# 00_ESP8266_CH340.net
KiCad netlist of a schematic drawn in Altium Designer
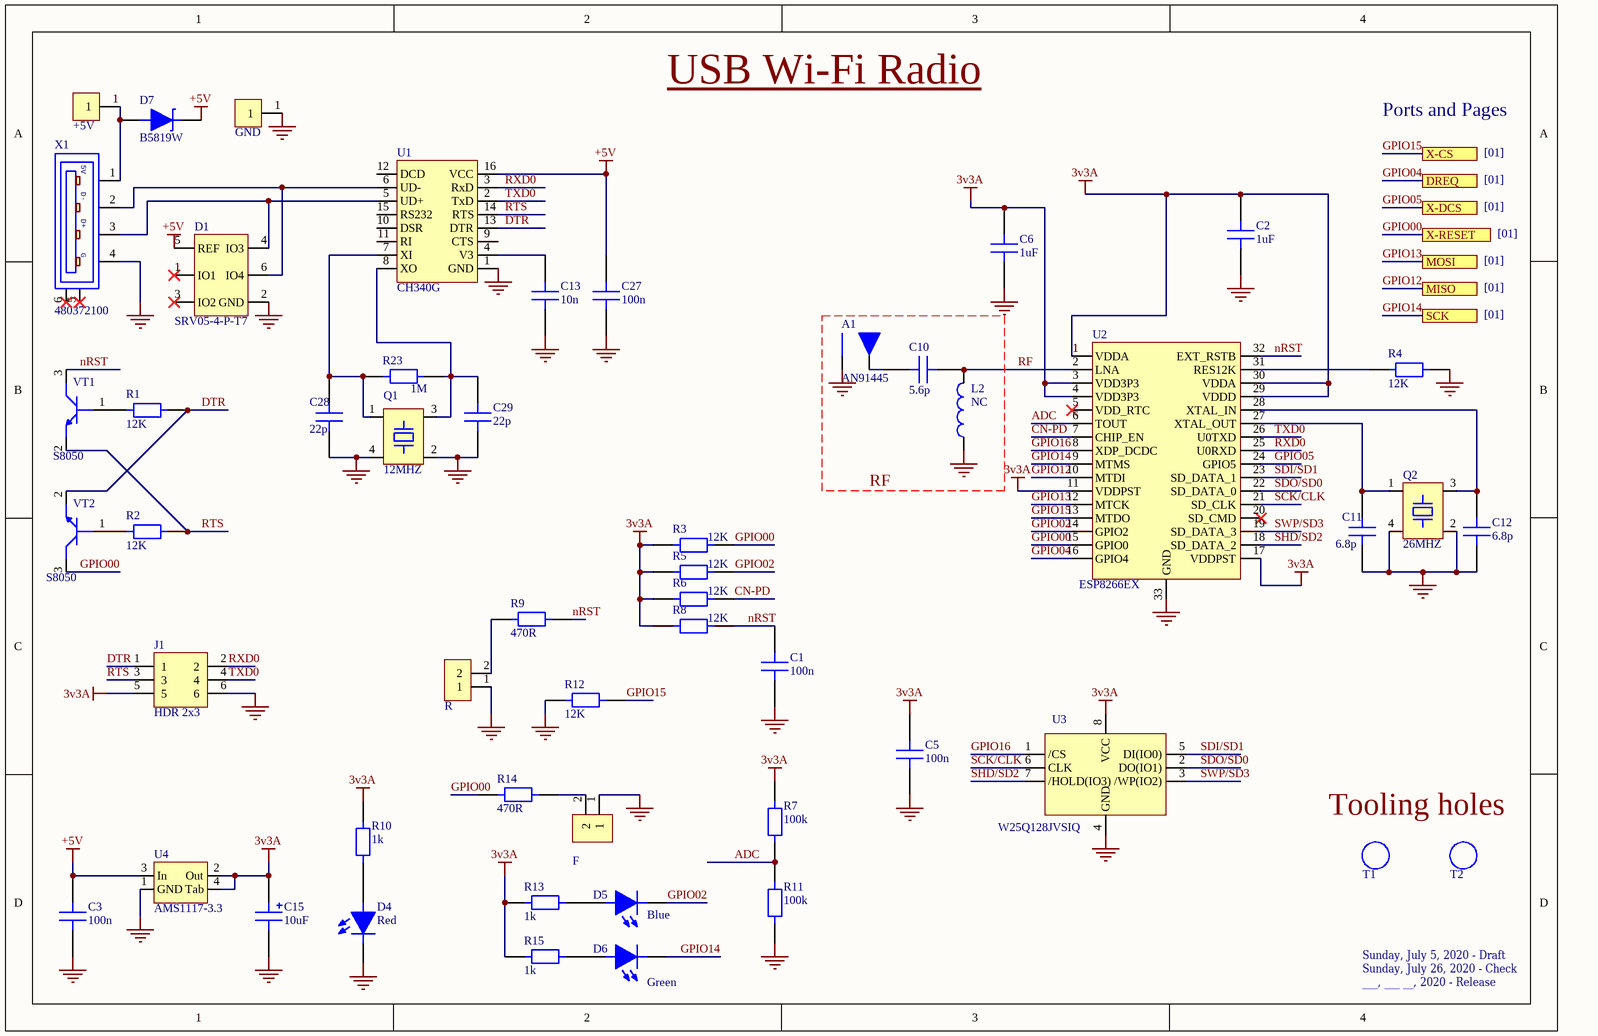
[diagram p0: [00] ESP8266 CH340.SchDoc]

(export (version "E")
  (design (tool "Eeschema 10.0.6"))
  (components
    (comp (ref "A1")
      (value "AN91445")
      (footprint "MIFA 2.4GHz")
      (libsource (lib "WiFi_Lib") (part "MIFA 2.4GHz"))
    )
    (comp (ref "C1")
      (value "100n")
      (footprint "0603 CAP")
      (description "MULTILAYER CERAMIC CAPACITORS MLCC - SMD/SMT 100NF 50V 0603 ROHS")
      (fields (field (name "MANUFACTURER") "YAGEO") (field (name "MFR.PART #") "CC0603KRX7R9BB104"))
      (libsource (lib "JLC_Lib") (part "CC0603KRX7R9BB104"))
    )
    (comp (ref "C2")
      (value "1uF")
      (footprint "0402")
      (description "MULTILAYER CERAMIC CAPACITORS MLCC - SMD/SMT 1UF 25V 0402 ROHS")
      (fields
        (field (name "MANUFACTURER") "Samsung Electro-Mechanics")
        (field (name "MFR.PART #") "CL05A105KA5NQNC")
      )
      (libsource (lib "JLC_Lib") (part "CL05A105KA5NQNC"))
    )
    (comp (ref "C3")
      (value "100n")
      (footprint "0603 CAP")
      (description "MULTILAYER CERAMIC CAPACITORS MLCC - SMD/SMT 100NF 50V 0603 ROHS")
      (fields (field (name "MANUFACTURER") "YAGEO") (field (name "MFR.PART #") "CC0603KRX7R9BB104"))
      (libsource (lib "JLC_Lib") (part "CC0603KRX7R9BB104"))
    )
    (comp (ref "C5")
      (value "100n")
      (footprint "0603 CAP")
      (description "MULTILAYER CERAMIC CAPACITORS MLCC - SMD/SMT 100NF 50V 0603 ROHS")
      (fields (field (name "MANUFACTURER") "YAGEO") (field (name "MFR.PART #") "CC0603KRX7R9BB104"))
      (libsource (lib "JLC_Lib") (part "CC0603KRX7R9BB104"))
    )
    (comp (ref "C6")
      (value "1uF")
      (footprint "0402")
      (description "MULTILAYER CERAMIC CAPACITORS MLCC - SMD/SMT 1UF 25V 0402 ROHS")
      (fields
        (field (name "MANUFACTURER") "Samsung Electro-Mechanics")
        (field (name "MFR.PART #") "CL05A105KA5NQNC")
      )
      (libsource (lib "JLC_Lib") (part "CL05A105KA5NQNC"))
    )
    (comp (ref "C10")
      (value "5.6p")
      (footprint "CAP 0402")
      (description "5.6PF ±0.25PF 50V C0G 0402 MULTILAYER CERAMIC CAPACITORS MLCC - SMD/SMT ROHS")
      (fields
        (field (name "MANUFACTURER") "Samsung Electro-Mechanics")
        (field (name "MFR.PART #") "CL05C5R6CB5NNNC")
      )
      (libsource (lib "JLC_Lib") (part "CL05B103KB5NNNC_1"))
    )
    (comp (ref "C11")
      (value "6.8p")
      (footprint "0402")
      (description "MULTILAYER CERAMIC CAPACITORS MLCC - SMD/SMT 6.8PF 50V 0402 ROHS")
      (fields
        (field (name "MANUFACTURER") "Guangdong Fenghua Advanced Tech")
        (field (name "MFR.PART #") "0402CG6R8C500NT")
      )
      (libsource (lib "JLC_Lib") (part "0402CG6R8C500NT"))
    )
    (comp (ref "C12")
      (value "6.8p")
      (footprint "0402")
      (description "MULTILAYER CERAMIC CAPACITORS MLCC - SMD/SMT 6.8PF 50V 0402 ROHS")
      (fields
        (field (name "MANUFACTURER") "Guangdong Fenghua Advanced Tech")
        (field (name "MFR.PART #") "0402CG6R8C500NT")
      )
      (libsource (lib "JLC_Lib") (part "0402CG6R8C500NT"))
    )
    (comp (ref "C13")
      (value "10n")
      (footprint "0603 CAP")
      (description "MULTILAYER CERAMIC CAPACITORS MLCC - SMD/SMT 10NF 50V 0603 ROHS")
      (fields
        (field (name "MANUFACTURER") "Guangdong Fenghua Advanced Tech")
        (field (name "MFR.PART #") "0603B103K500NT")
      )
      (libsource (lib "JLC_Lib") (part "0603B103K500NT"))
    )
    (comp (ref "C15")
      (value "10uF")
      (footprint "CAP 1206")
      (description "TANTALUM CAPACITORS 10UF 16V CASE-A_3216 ROHS")
      (fields (field (name "MANUFACTURER") "AVX") (field (name "MFR.PART #") "TAJA106K016RNJ"))
      (libsource (lib "JLC_Lib") (part "TAJA106K016RNJ"))
    )
    (comp (ref "C27")
      (value "100n")
      (footprint "0603 CAP")
      (description "MULTILAYER CERAMIC CAPACITORS MLCC - SMD/SMT 100NF 50V 0603 ROHS")
      (fields (field (name "MANUFACTURER") "YAGEO") (field (name "MFR.PART #") "CC0603KRX7R9BB104"))
      (libsource (lib "JLC_Lib") (part "CC0603KRX7R9BB104"))
    )
    (comp (ref "C28")
      (value "22p")
      (footprint "0603 CAP")
      (description "MULTILAYER CERAMIC CAPACITORS MLCC - SMD/SMT 22PF 50V 0603 ROHS")
      (fields
        (field (name "MANUFACTURER") "Samsung Electro-Mechanics")
        (field (name "MFR.PART #") "CL10C220JB8NNNC")
      )
      (libsource (lib "JLC_Lib") (part "CL10C220JB8NNNC"))
    )
    (comp (ref "C29")
      (value "22p")
      (footprint "0603 CAP")
      (description "MULTILAYER CERAMIC CAPACITORS MLCC - SMD/SMT 22PF 50V 0603 ROHS")
      (fields
        (field (name "MANUFACTURER") "Samsung Electro-Mechanics")
        (field (name "MFR.PART #") "CL10C220JB8NNNC")
      )
      (libsource (lib "JLC_Lib") (part "CL10C220JB8NNNC"))
    )
    (comp (ref "D1")
      (value "SRV05-4-P-T7")
      (footprint "SOT-23-6")
      (description "TVS SOT-23-6 ROHS")
      (fields (field (name "MANUFACTURER") "ProTek Devices") (field (name "LCSC PART #") "C85364"))
      (libsource (lib "JLC_Lib") (part "SRV05-4-P-T7"))
    )
    (comp (ref "D4")
      (value "Red")
      (footprint "LED 0603")
      (description "LIGHT EMITTING DIODES (LED) RED 520~625NM 90~100MCD@20MA TOP VIEW 0603 ROHS")
      (fields (field (name "MANUFACTURER") "Hubei KENTO Elec") (field (name "MFR.PART #") "KT-0603R"))
      (libsource (lib "JLC_Lib") (part "KT-0603R"))
    )
    (comp (ref "D5")
      (value "Blue")
      (footprint "LED 0603")
      (description "LIGHT EMITTING DIODES (LED) BLUE 465~475NM 11.5~28.5MCD@5MA TOP VIEW 0603 ROHS")
      (fields
        (field (name "MANUFACTURER") "Everlight Elec")
        (field (name "MFR.PART #") "19-217/BHC-ZL1M2RY/3T")
      )
      (libsource (lib "JLC_Lib") (part "19-217/BHC-ZL1M2RY/3T"))
    )
    (comp (ref "D6")
      (value "Green")
      (footprint "LED 0603")
      (description "LIGHT EMITTING DIODES (LED) GREEN 520~535NM 112~258MCD@20MA TOP VIEW 0603 ROHS")
      (fields
        (field (name "MANUFACTURER") "Everlight Elec")
        (field (name "MFR.PART #") "19-217/GHC-YR1S2/3T")
      )
      (libsource (lib "JLC_Lib") (part "19-217/GHC-YR1S2/3T"))
    )
    (comp (ref "D7")
      (value "B5819W")
      (footprint "SOD-123")
      (description "SCHOTTKY BARRIER DIODES (SBD) SOD-123 ROHS")
      (fields
        (field (name "MANUFACTURER") "Changjiang Electronics Tech (CJ)")
        (field (name "LCSC PART #") "C8598")
      )
      (libsource (lib "JLC_Lib") (part "B5819W"))
    )
    (comp (ref "J1")
      (value "HDR 2x3")
      (footprint "HDR 2x3 2.54mm")
      (description "CONN HEADER 6POS .100 STR 30AU")
      (libsource (lib "WiFi_Lib") (part "67997-106HLF"))
    )
    (comp (ref "JP1")
      (value "R")
      (footprint "Hdr_Fem_1x2_2.54mm")
      (description "CONN HEADER VERT 2POS 2.54MM")
      (libsource (lib "WiFi_Lib") (part "68602-204HLF"))
    )
    (comp (ref "JP2")
      (value "F")
      (footprint "Hdr_Fem_1x2_2.54mm")
      (description "CONN HEADER VERT 2POS 2.54MM")
      (libsource (lib "") (part "68602-204HLF_1"))
    )
    (comp (ref "JP3")
      (value "+5V")
      (footprint "Hdr_Fem_1x1_2.54mm")
      (description "CONN HEADER VERT 1POS 2.54MM")
      (libsource (lib "WiFi_Lib") (part "68602-101HLF"))
    )
    (comp (ref "JP4")
      (value "GND")
      (footprint "Hdr_Fem_1x1_2.54mm")
      (description "CONN HEADER VERT 1POS 2.54MM")
      (libsource (lib "WiFi_Lib") (part "68602-101HLF"))
    )
    (comp (ref "L2")
      (value "NC")
      (footprint "IND 0402")
      (description "IND 0402 Matching")
      (libsource (lib "WiFi_Lib") (part "NC IND"))
    )
    (comp (ref "Q1")
      (value "12MHZ")
      (footprint "ABM8W")
      (description "SMD CRYSTAL RESONATORS 12MHZ ±10PPM SMD-3225_4P ROHS")
      (fields (field (name "MANUFACTURER") "Yangxing Tech") (field (name "MFR.PART #") "X322512MSB4SI"))
      (libsource (lib "JLC_Lib") (part "X322512MSB4SI"))
    )
    (comp (ref "Q2")
      (value "26MHZ")
      (footprint "ABM8W")
      (description "SMD CRYSTAL RESONATORS 26MHZ ±10PPM SMD-3225_4P ROHS")
      (fields (field (name "MANUFACTURER") "Yangxing Tech") (field (name "MFR.PART #") "X322526MEB4SC"))
      (libsource (lib "JLC_Lib") (part "X322526MEB4SC"))
    )
    (comp (ref "R1")
      (value "12K")
      (footprint "0603 RES")
      (description "CHIP RESISTOR - SURFACE MOUNT 12KOHMS ±1% 1/10W 0603 ROHS")
      (fields (field (name "MANUFACTURER") "Uniroyal Elec") (field (name "MFR.PART #") "0603WAF1202T5E"))
      (libsource (lib "JLC_Lib") (part "0603WAF1202T5E"))
    )
    (comp (ref "R2")
      (value "12K")
      (footprint "0603 RES")
      (description "CHIP RESISTOR - SURFACE MOUNT 12KOHMS ±1% 1/10W 0603 ROHS")
      (fields (field (name "MANUFACTURER") "Uniroyal Elec") (field (name "MFR.PART #") "0603WAF1202T5E"))
      (libsource (lib "JLC_Lib") (part "0603WAF1202T5E"))
    )
    (comp (ref "R3")
      (value "12K")
      (footprint "0603 RES")
      (description "CHIP RESISTOR - SURFACE MOUNT 12KOHMS ±1% 1/10W 0603 ROHS")
      (fields (field (name "MANUFACTURER") "Uniroyal Elec") (field (name "MFR.PART #") "0603WAF1202T5E"))
      (libsource (lib "JLC_Lib") (part "0603WAF1202T5E"))
    )
    (comp (ref "R4")
      (value "12K")
      (footprint "0402 RES")
      (description "CHIP RESISTOR - SURFACE MOUNT 12KOHMS ±1% 1/16W 0402 ROHS")
      (fields (field (name "MANUFACTURER") "Uniroyal Elec") (field (name "MFR.PART #") "0402WGF1202TCE"))
      (libsource (lib "JLC_Lib") (part "0402WGF1202TCE"))
    )
    (comp (ref "R5")
      (value "12K")
      (footprint "0603 RES")
      (description "CHIP RESISTOR - SURFACE MOUNT 12KOHMS ±1% 1/10W 0603 ROHS")
      (fields (field (name "MANUFACTURER") "Uniroyal Elec") (field (name "MFR.PART #") "0603WAF1202T5E"))
      (libsource (lib "JLC_Lib") (part "0603WAF1202T5E"))
    )
    (comp (ref "R6")
      (value "12K")
      (footprint "0603 RES")
      (description "CHIP RESISTOR - SURFACE MOUNT 12KOHMS ±1% 1/10W 0603 ROHS")
      (fields (field (name "MANUFACTURER") "Uniroyal Elec") (field (name "MFR.PART #") "0603WAF1202T5E"))
      (libsource (lib "JLC_Lib") (part "0603WAF1202T5E"))
    )
    (comp (ref "R7")
      (value "100k")
      (footprint "0603 RES")
      (description "CHIP RESISTOR - SURFACE MOUNT 100KOHMS ±1% 1/10W 0603 ROHS")
      (fields (field (name "MANUFACTURER") "Uniroyal Elec") (field (name "MFR.PART #") "0603WAF1003T5E"))
      (libsource (lib "JLC_Lib") (part "0603WAF1003T5E"))
    )
    (comp (ref "R8")
      (value "12K")
      (footprint "0603 RES")
      (description "CHIP RESISTOR - SURFACE MOUNT 12KOHMS ±1% 1/10W 0603 ROHS")
      (fields (field (name "MANUFACTURER") "Uniroyal Elec") (field (name "MFR.PART #") "0603WAF1202T5E"))
      (libsource (lib "JLC_Lib") (part "0603WAF1202T5E"))
    )
    (comp (ref "R9")
      (value "470R")
      (footprint "0603 RES")
      (description "CHIP RESISTOR - SURFACE MOUNT 470OHMS ±1% 1/10W 0603 ROHS")
      (fields (field (name "MANUFACTURER") "Uniroyal Elec") (field (name "MFR.PART #") "0603WAF4700T5E"))
      (libsource (lib "JLC_Lib") (part "0603WAF4700T5E"))
    )
    (comp (ref "R10")
      (value "1k")
      (footprint "0603 RES")
      (description "CHIP RESISTOR - SURFACE MOUNT 1KOHMS ±1% 1/10W 0603 ROHS")
      (fields (field (name "MANUFACTURER") "Uniroyal Elec") (field (name "MFR.PART #") "0603WAF1001T5E"))
      (libsource (lib "JLC_Lib") (part "0603WAF1001T5E"))
    )
    (comp (ref "R11")
      (value "100k")
      (footprint "0603 RES")
      (description "CHIP RESISTOR - SURFACE MOUNT 100KOHMS ±1% 1/10W 0603 ROHS")
      (fields (field (name "MANUFACTURER") "Uniroyal Elec") (field (name "MFR.PART #") "0603WAF1003T5E"))
      (libsource (lib "JLC_Lib") (part "0603WAF1003T5E"))
    )
    (comp (ref "R12")
      (value "12K")
      (footprint "0603 RES")
      (description "CHIP RESISTOR - SURFACE MOUNT 12KOHMS ±1% 1/10W 0603 ROHS")
      (fields (field (name "MANUFACTURER") "Uniroyal Elec") (field (name "MFR.PART #") "0603WAF1202T5E"))
      (libsource (lib "JLC_Lib") (part "0603WAF1202T5E"))
    )
    (comp (ref "R13")
      (value "1k")
      (footprint "0603 RES")
      (description "CHIP RESISTOR - SURFACE MOUNT 1KOHMS ±1% 1/10W 0603 ROHS")
      (fields (field (name "MANUFACTURER") "Uniroyal Elec") (field (name "MFR.PART #") "0603WAF1001T5E"))
      (libsource (lib "JLC_Lib") (part "0603WAF1001T5E"))
    )
    (comp (ref "R14")
      (value "470R")
      (footprint "0603 RES")
      (description "CHIP RESISTOR - SURFACE MOUNT 470OHMS ±1% 1/10W 0603 ROHS")
      (fields (field (name "MANUFACTURER") "Uniroyal Elec") (field (name "MFR.PART #") "0603WAF4700T5E"))
      (libsource (lib "JLC_Lib") (part "0603WAF4700T5E"))
    )
    (comp (ref "R15")
      (value "1k")
      (footprint "0603 RES")
      (description "CHIP RESISTOR - SURFACE MOUNT 1KOHMS ±1% 1/10W 0603 ROHS")
      (fields (field (name "MANUFACTURER") "Uniroyal Elec") (field (name "MFR.PART #") "0603WAF1001T5E"))
      (libsource (lib "JLC_Lib") (part "0603WAF1001T5E"))
    )
    (comp (ref "R23")
      (value "1M")
      (footprint "0603 RES")
      (description "CHIP RESISTOR - SURFACE MOUNT 1MOHMS ±1% 1/10W 0603 ROHS")
      (fields (field (name "MANUFACTURER") "Uniroyal Elec") (field (name "MFR.PART #") "0603WAF1004T5E"))
      (libsource (lib "JLC_Lib") (part "0603WAF1004T5E"))
    )
    (comp (ref "T1")
      (value "Tooling hole")
      (footprint "Tooling")
      (description "For JLCPCB SMT Assembly")
      (libsource (lib "JLC_Lib") (part "Tooling hole"))
    )
    (comp (ref "T2")
      (value "Tooling hole")
      (footprint "Tooling")
      (description "For JLCPCB SMT Assembly")
      (libsource (lib "JLC_Lib") (part "Tooling hole"))
    )
    (comp (ref "U1")
      (value "CH340G")
      (footprint "SOP-16")
      (description "USB 2MBPS 3.3V, 5V SOP-16_150MIL ROHS")
      (fields (field (name "MANUFACTURER") "Jiangsu Qin Heng") (field (name "LCSC PART #") "C14267"))
      (libsource (lib "JLC_Lib") (part "CH340G"))
    )
    (comp (ref "U2")
      (value "ESP8266EX")
      (footprint "QFN-32 Thermal")
      (fields (field (name "MANUFACTURER") "Espressif Systems") (field (name "LCSC PART #") "C77967"))
      (libsource (lib "JLC_Lib") (part "ESP8266EX"))
    )
    (comp (ref "U3")
      (value "W25Q128JVSIQ")
      (footprint "SOIC-8 208-mil")
      (description "FLASH FLASH 128MB (16M X 8) SPI - DUAL/QUAD I/O SOIC-8_208MIL ROHS")
      (fields (field (name "MANUFACTURER") "Winbond Elec") (field (name "LCSC PART #") "C97521"))
      (libsource (lib "JLC_Lib") (part "W25Q128JVSIQ"))
    )
    (comp (ref "U4")
      (value "AMS1117-3.3")
      (footprint "SOT233-3")
      (description "LOW DROPOUT REGULATORS(LDO) POSITIVE FIXED 1.3V @ 800MA 15V 3.3V 1A SOT-223 ROHS")
      (fields
        (field (name "MANUFACTURER") "Advanced Monolithic Systems")
        (field (name "LCSC PART #") "C6186")
      )
      (libsource (lib "JLC_Lib") (part "AMS1117-3.3"))
    )
    (comp (ref "VT1")
      (value "S8050")
      (footprint "SOT-23")
      (description "TRANSISTORS (NPN/PNP) NPN 500MA 25V SOT-23(SOT-23-3) ROHS")
      (fields
        (field (name "MANUFACTURER") "Changjiang Electronics Tech (CJ)")
        (field (name "LCSC PART #") "C2146")
      )
      (libsource (lib "JLC_Lib") (part "S8050"))
    )
    (comp (ref "VT2")
      (value "S8050")
      (footprint "SOT-23")
      (description "TRANSISTORS (NPN/PNP) NPN 500MA 25V SOT-23(SOT-23-3) ROHS")
      (fields
        (field (name "MANUFACTURER") "Changjiang Electronics Tech (CJ)")
        (field (name "LCSC PART #") "C2146")
      )
      (libsource (lib "JLC_Lib") (part "S8050"))
    )
    (comp (ref "X1")
      (value "480372100")
      (footprint "USB2.0-A")
      (description "USB - Type A Male USB 2 4 Through Hole USB Connectors RoHS")
      (fields (field (name "MANUFACTURER") "MOLEX") (field (name "LCSC PART #") "C136453"))
      (libsource (lib "JLC_Lib") (part "480372100"))
    )
  )
  (nets
    (net (code "1") (name "+5V") (class "Default")
      (node (ref "C27") (pin "2") (pinfunction "2_2") (pintype "passive"))
      (node (ref "C3") (pin "2") (pinfunction "2_2") (pintype "passive"))
      (node (ref "D1") (pin "5") (pinfunction "REF_5") (pintype "passive"))
      (node (ref "D7") (pin "2") (pinfunction "K_2") (pintype "passive"))
      (node (ref "U1") (pin "16") (pinfunction "VCC_16") (pintype "passive"))
      (node (ref "U4") (pin "3") (pinfunction "In_3") (pintype "passive"))
    )
    (net (code "2") (name "/ADC") (class "Default")
      (node (ref "R11") (pin "2") (pinfunction "2_2") (pintype "passive"))
      (node (ref "R7") (pin "1") (pinfunction "1_1") (pintype "passive"))
      (node (ref "U2") (pin "6") (pinfunction "TOUT_6") (pintype "passive"))
    )
    (net (code "3") (name "/CN-PD") (class "Default")
      (node (ref "R6") (pin "2") (pinfunction "2_2") (pintype "passive"))
      (node (ref "U2") (pin "7") (pinfunction "CHIP_EN_7") (pintype "passive"))
    )
    (net (code "4") (name "/DTR") (class "Default")
      (node (ref "J1") (pin "1") (pinfunction "1_1") (pintype "passive"))
      (node (ref "R1") (pin "2") (pinfunction "2_2") (pintype "passive"))
      (node (ref "U1") (pin "13") (pinfunction "DTR_13") (pintype "passive"))
      (node (ref "VT2") (pin "2") (pinfunction "2_2") (pintype "passive"))
    )
    (net (code "5") (name "/GPIO00") (class "Default")
      (node (ref "R14") (pin "1") (pinfunction "1_1") (pintype "passive"))
      (node (ref "R3") (pin "2") (pinfunction "2_2") (pintype "passive"))
      (node (ref "U2") (pin "15") (pinfunction "GPIO0_15") (pintype "passive"))
      (node (ref "VT2") (pin "3") (pinfunction "3_3") (pintype "passive"))
    )
    (net (code "6") (name "/GPIO02") (class "Default")
      (node (ref "D5") (pin "2") (pinfunction "2_2") (pintype "passive"))
      (node (ref "R5") (pin "2") (pinfunction "2_2") (pintype "passive"))
      (node (ref "U2") (pin "14") (pinfunction "GPIO2_14") (pintype "passive"))
    )
    (net (code "7") (name "/GPIO04") (class "Default")
      (node (ref "U2") (pin "16") (pinfunction "GPIO4_16") (pintype "passive"))
    )
    (net (code "8") (name "/GPIO05") (class "Default")
      (node (ref "U2") (pin "24") (pinfunction "GPIO5_24") (pintype "passive"))
    )
    (net (code "9") (name "/GPIO12") (class "Default")
      (node (ref "U2") (pin "10") (pinfunction "MTDI_10") (pintype "passive"))
    )
    (net (code "10") (name "/GPIO13") (class "Default")
      (node (ref "U2") (pin "12") (pinfunction "MTCK_12") (pintype "passive"))
    )
    (net (code "11") (name "/GPIO14") (class "Default")
      (node (ref "D6") (pin "2") (pinfunction "2_2") (pintype "passive"))
      (node (ref "U2") (pin "9") (pinfunction "MTMS_9") (pintype "passive"))
    )
    (net (code "12") (name "/GPIO15") (class "Default")
      (node (ref "R12") (pin "2") (pinfunction "2_2") (pintype "passive"))
      (node (ref "U2") (pin "13") (pinfunction "MTDO_13") (pintype "passive"))
    )
    (net (code "13") (name "/GPIO16") (class "Default")
      (node (ref "U2") (pin "8") (pinfunction "XDP_DCDC_8") (pintype "passive"))
      (node (ref "U3") (pin "1") (pinfunction "/CS_1") (pintype "passive"))
    )
    (net (code "14") (name "/RF") (class "Default")
      (node (ref "C10") (pin "2") (pinfunction "2_2") (pintype "passive"))
      (node (ref "L2") (pin "2") (pinfunction "2_2") (pintype "passive"))
      (node (ref "U2") (pin "2") (pinfunction "LNA_2") (pintype "passive"))
    )
    (net (code "15") (name "/RTS") (class "Default")
      (node (ref "J1") (pin "3") (pinfunction "3_3") (pintype "passive"))
      (node (ref "R2") (pin "2") (pinfunction "2_2") (pintype "passive"))
      (node (ref "U1") (pin "14") (pinfunction "RTS_14") (pintype "passive"))
      (node (ref "VT1") (pin "2") (pinfunction "2_2") (pintype "passive"))
    )
    (net (code "16") (name "/RXD0") (class "Default")
      (node (ref "J1") (pin "2") (pinfunction "2_2") (pintype "passive"))
      (node (ref "U1") (pin "3") (pinfunction "RxD_3") (pintype "passive"))
      (node (ref "U2") (pin "25") (pinfunction "U0RXD_25") (pintype "passive"))
    )
    (net (code "17") (name "/SCK{slash}CLK") (class "Default")
      (node (ref "U2") (pin "21") (pinfunction "SD_CLK_21") (pintype "passive"))
      (node (ref "U3") (pin "6") (pinfunction "CLK_6") (pintype "passive"))
    )
    (net (code "18") (name "/SDI{slash}SD1") (class "Default")
      (node (ref "U2") (pin "23") (pinfunction "SD_DATA_1_23") (pintype "passive"))
      (node (ref "U3") (pin "5") (pinfunction "DI(IO0)_5") (pintype "passive"))
    )
    (net (code "19") (name "/SDO{slash}SD0") (class "Default")
      (node (ref "U2") (pin "22") (pinfunction "SD_DATA_0_22") (pintype "passive"))
      (node (ref "U3") (pin "2") (pinfunction "DO(IO1)_2") (pintype "passive"))
    )
    (net (code "20") (name "/SHD{slash}SD2") (class "Default")
      (node (ref "U2") (pin "18") (pinfunction "SD_DATA_2_18") (pintype "passive"))
      (node (ref "U3") (pin "7") (pinfunction "/HOLD(IO3)_7") (pintype "passive"))
    )
    (net (code "21") (name "/SWP{slash}SD3") (class "Default")
      (node (ref "U2") (pin "19") (pinfunction "SD_DATA_3_19") (pintype "passive"))
      (node (ref "U3") (pin "3") (pinfunction "/WP(IO2)_3") (pintype "passive"))
    )
    (net (code "22") (name "/TXD0") (class "Default")
      (node (ref "J1") (pin "4") (pinfunction "4_4") (pintype "passive"))
      (node (ref "U1") (pin "2") (pinfunction "TxD_2") (pintype "passive"))
      (node (ref "U2") (pin "26") (pinfunction "U0TXD_26") (pintype "passive"))
    )
    (net (code "23") (name "/nRST") (class "Default")
      (node (ref "C1") (pin "2") (pinfunction "2_2") (pintype "passive"))
      (node (ref "R8") (pin "2") (pinfunction "2_2") (pintype "passive"))
      (node (ref "R9") (pin "2") (pinfunction "2_2") (pintype "passive"))
      (node (ref "U2") (pin "32") (pinfunction "EXT_RSTB_32") (pintype "passive"))
      (node (ref "VT1") (pin "3") (pinfunction "3_3") (pintype "passive"))
    )
    (net (code "24") (name "3v3A") (class "Default")
      (node (ref "C15") (pin "1") (pinfunction "1_1") (pintype "passive"))
      (node (ref "C2") (pin "2") (pinfunction "2_2") (pintype "passive"))
      (node (ref "C5") (pin "1") (pinfunction "1_1") (pintype "passive"))
      (node (ref "C6") (pin "2") (pinfunction "2_2") (pintype "passive"))
      (node (ref "J1") (pin "5") (pinfunction "5_5") (pintype "passive"))
      (node (ref "R10") (pin "2") (pinfunction "2_2") (pintype "passive"))
      (node (ref "R13") (pin "1") (pinfunction "1_1") (pintype "passive"))
      (node (ref "R15") (pin "1") (pinfunction "1_1") (pintype "passive"))
      (node (ref "R3") (pin "1") (pinfunction "1_1") (pintype "passive"))
      (node (ref "R5") (pin "1") (pinfunction "1_1") (pintype "passive"))
      (node (ref "R6") (pin "1") (pinfunction "1_1") (pintype "passive"))
      (node (ref "R7") (pin "2") (pinfunction "2_2") (pintype "passive"))
      (node (ref "R8") (pin "1") (pinfunction "1_1") (pintype "passive"))
      (node (ref "U2") (pin "1") (pinfunction "VDDA_1") (pintype "passive"))
      (node (ref "U2") (pin "11") (pinfunction "VDDPST_11") (pintype "passive"))
      (node (ref "U2") (pin "17") (pinfunction "VDDPST_17") (pintype "passive"))
      (node (ref "U2") (pin "29") (pinfunction "VDDD_29") (pintype "passive"))
      (node (ref "U2") (pin "3") (pinfunction "VDD3P3_3") (pintype "passive"))
      (node (ref "U2") (pin "30") (pinfunction "VDDA_30") (pintype "passive"))
      (node (ref "U2") (pin "4") (pinfunction "VDD3P3_4") (pintype "passive"))
      (node (ref "U3") (pin "8") (pinfunction "VCC_8") (pintype "passive"))
      (node (ref "U4") (pin "2") (pinfunction "Out_2") (pintype "passive"))
      (node (ref "U4") (pin "4") (pinfunction "Tab_4") (pintype "passive"))
    )
    (net (code "25") (name "GND") (class "Default")
      (node (ref "A1") (pin "2") (pinfunction "2_2") (pintype "passive"))
      (node (ref "C1") (pin "1") (pinfunction "1_1") (pintype "passive"))
      (node (ref "C11") (pin "1") (pinfunction "1_1") (pintype "passive"))
      (node (ref "C12") (pin "1") (pinfunction "1_1") (pintype "passive"))
      (node (ref "C13") (pin "1") (pinfunction "1_1") (pintype "passive"))
      (node (ref "C15") (pin "2") (pinfunction "2_2") (pintype "passive"))
      (node (ref "C2") (pin "1") (pinfunction "1_1") (pintype "passive"))
      (node (ref "C27") (pin "1") (pinfunction "1_1") (pintype "passive"))
      (node (ref "C28") (pin "1") (pinfunction "1_1") (pintype "passive"))
      (node (ref "C29") (pin "1") (pinfunction "1_1") (pintype "passive"))
      (node (ref "C3") (pin "1") (pinfunction "1_1") (pintype "passive"))
      (node (ref "C5") (pin "2") (pinfunction "2_2") (pintype "passive"))
      (node (ref "C6") (pin "1") (pinfunction "1_1") (pintype "passive"))
      (node (ref "D1") (pin "2") (pinfunction "GND_2") (pintype "passive"))
      (node (ref "D4") (pin "2") (pinfunction "2_2") (pintype "passive"))
      (node (ref "J1") (pin "6") (pinfunction "6_6") (pintype "passive"))
      (node (ref "JP1") (pin "1") (pinfunction "1_1") (pintype "passive"))
      (node (ref "JP2") (pin "1") (pinfunction "1_1") (pintype "passive"))
      (node (ref "JP4") (pin "1") (pinfunction "1_1") (pintype "passive"))
      (node (ref "L2") (pin "1") (pinfunction "1_1") (pintype "passive"))
      (node (ref "Q1") (pin "2") (pinfunction "GND_2") (pintype "passive"))
      (node (ref "Q1") (pin "4") (pinfunction "GND_4") (pintype "passive"))
      (node (ref "Q2") (pin "2") (pinfunction "GND_2") (pintype "passive"))
      (node (ref "Q2") (pin "4") (pinfunction "GND_4") (pintype "passive"))
      (node (ref "R11") (pin "1") (pinfunction "1_1") (pintype "passive"))
      (node (ref "R12") (pin "1") (pinfunction "1_1") (pintype "passive"))
      (node (ref "R4") (pin "2") (pinfunction "2_2") (pintype "passive"))
      (node (ref "U1") (pin "1") (pinfunction "GND_1") (pintype "passive"))
      (node (ref "U2") (pin "33") (pinfunction "GND_33") (pintype "passive"))
      (node (ref "U3") (pin "4") (pinfunction "GND_4") (pintype "passive"))
      (node (ref "U4") (pin "1") (pinfunction "GND_1") (pintype "passive"))
      (node (ref "X1") (pin "4") (pinfunction "GND_4") (pintype "passive"))
    )
    (net (code "26") (name "Net-(A1-Pad1)") (class "Default")
      (node (ref "A1") (pin "1") (pinfunction "1_1") (pintype "passive"))
      (node (ref "C10") (pin "1") (pinfunction "1_1") (pintype "passive"))
    )
    (net (code "27") (name "Net-(D1-IO3)") (class "Default")
      (node (ref "D1") (pin "4") (pinfunction "IO3_4") (pintype "passive"))
      (node (ref "U1") (pin "5") (pinfunction "UD+_5") (pintype "passive"))
      (node (ref "X1") (pin "3") (pinfunction "DX_P_3") (pintype "passive"))
    )
    (net (code "28") (name "Net-(D1-IO4)") (class "Default")
      (node (ref "D1") (pin "6") (pinfunction "IO4_6") (pintype "passive"))
      (node (ref "U1") (pin "6") (pinfunction "UD-_6") (pintype "passive"))
      (node (ref "X1") (pin "2") (pinfunction "DX_N_2") (pintype "passive"))
    )
    (net (code "29") (name "Net-(D4-Pad1)") (class "Default")
      (node (ref "D4") (pin "1") (pinfunction "1_1") (pintype "passive"))
      (node (ref "R10") (pin "1") (pinfunction "1_1") (pintype "passive"))
    )
    (net (code "30") (name "Net-(D5-Pad1)") (class "Default")
      (node (ref "D5") (pin "1") (pinfunction "1_1") (pintype "passive"))
      (node (ref "R13") (pin "2") (pinfunction "2_2") (pintype "passive"))
    )
    (net (code "31") (name "Net-(D6-Pad1)") (class "Default")
      (node (ref "D6") (pin "1") (pinfunction "1_1") (pintype "passive"))
      (node (ref "R15") (pin "2") (pinfunction "2_2") (pintype "passive"))
    )
    (net (code "32") (name "Net-(D7-A)") (class "Default")
      (node (ref "D7") (pin "1") (pinfunction "A_1") (pintype "passive"))
      (node (ref "JP3") (pin "1") (pinfunction "1_1") (pintype "passive"))
      (node (ref "X1") (pin "1") (pinfunction "5V_1") (pintype "passive"))
    )
    (net (code "33") (name "Net-(JP1-Pad2)") (class "Default")
      (node (ref "JP1") (pin "2") (pinfunction "2_2") (pintype "passive"))
      (node (ref "R9") (pin "1") (pinfunction "1_1") (pintype "passive"))
    )
    (net (code "34") (name "Net-(JP2-Pad2)") (class "Default")
      (node (ref "JP2") (pin "2") (pinfunction "2_2") (pintype "passive"))
      (node (ref "R14") (pin "2") (pinfunction "2_2") (pintype "passive"))
    )
    (net (code "35") (name "Net-(R1-Pad1)") (class "Default")
      (node (ref "R1") (pin "1") (pinfunction "1_1") (pintype "passive"))
      (node (ref "VT1") (pin "1") (pinfunction "1_1") (pintype "passive"))
    )
    (net (code "36") (name "Net-(R2-Pad1)") (class "Default")
      (node (ref "R2") (pin "1") (pinfunction "1_1") (pintype "passive"))
      (node (ref "VT2") (pin "1") (pinfunction "1_1") (pintype "passive"))
    )
    (net (code "37") (name "Net-(U1-V3)") (class "Default")
      (node (ref "C13") (pin "2") (pinfunction "2_2") (pintype "passive"))
      (node (ref "U1") (pin "4") (pinfunction "V3_4") (pintype "passive"))
    )
    (net (code "38") (name "Net-(U1-XI)") (class "Default")
      (node (ref "C28") (pin "2") (pinfunction "2_2") (pintype "passive"))
      (node (ref "Q1") (pin "1") (pinfunction "1_1") (pintype "passive"))
      (node (ref "R23") (pin "1") (pinfunction "1_1") (pintype "passive"))
      (node (ref "U1") (pin "7") (pinfunction "XI_7") (pintype "passive"))
    )
    (net (code "39") (name "Net-(U1-XO)") (class "Default")
      (node (ref "C29") (pin "2") (pinfunction "2_2") (pintype "passive"))
      (node (ref "Q1") (pin "3") (pinfunction "3_3") (pintype "passive"))
      (node (ref "R23") (pin "2") (pinfunction "2_2") (pintype "passive"))
      (node (ref "U1") (pin "8") (pinfunction "XO_8") (pintype "passive"))
    )
    (net (code "40") (name "Net-(U2-RES12K)") (class "Default")
      (node (ref "R4") (pin "1") (pinfunction "1_1") (pintype "passive"))
      (node (ref "U2") (pin "31") (pinfunction "RES12K_31") (pintype "passive"))
    )
    (net (code "41") (name "Net-(U2-XTAL_IN)") (class "Default")
      (node (ref "C12") (pin "2") (pinfunction "2_2") (pintype "passive"))
      (node (ref "Q2") (pin "3") (pinfunction "3_3") (pintype "passive"))
      (node (ref "U2") (pin "28") (pinfunction "XTAL_IN_28") (pintype "passive"))
    )
    (net (code "42") (name "Net-(U2-XTAL_OUT)") (class "Default")
      (node (ref "C11") (pin "2") (pinfunction "2_2") (pintype "passive"))
      (node (ref "Q2") (pin "1") (pinfunction "1_1") (pintype "passive"))
      (node (ref "U2") (pin "27") (pinfunction "XTAL_OUT_27") (pintype "passive"))
    )
    (net (code "43") (name "unconnected-(D1-IO1-Pad1)") (class "Default")
      (node (ref "D1") (pin "1") (pinfunction "IO1_1") (pintype "passive+no_connect"))
    )
    (net (code "44") (name "unconnected-(D1-IO2-Pad3)") (class "Default")
      (node (ref "D1") (pin "3") (pinfunction "IO2_3") (pintype "passive+no_connect"))
    )
    (net (code "45") (name "unconnected-(U1-CTS-Pad9)") (class "Default")
      (node (ref "U1") (pin "9") (pinfunction "CTS_9") (pintype "passive"))
    )
    (net (code "46") (name "unconnected-(U1-DCD-Pad12)") (class "Default")
      (node (ref "U1") (pin "12") (pinfunction "DCD_12") (pintype "passive"))
    )
    (net (code "47") (name "unconnected-(U1-DSR-Pad10)") (class "Default")
      (node (ref "U1") (pin "10") (pinfunction "DSR_10") (pintype "passive"))
    )
    (net (code "48") (name "unconnected-(U1-RI-Pad11)") (class "Default")
      (node (ref "U1") (pin "11") (pinfunction "RI_11") (pintype "passive"))
    )
    (net (code "49") (name "unconnected-(U1-RS232-Pad15)") (class "Default")
      (node (ref "U1") (pin "15") (pinfunction "RS232_15") (pintype "passive"))
    )
    (net (code "50") (name "unconnected-(U2-SD_CMD-Pad20)") (class "Default")
      (node (ref "U2") (pin "20") (pinfunction "SD_CMD_20") (pintype "passive+no_connect"))
    )
    (net (code "51") (name "unconnected-(U2-VDD_RTC-Pad5)") (class "Default")
      (node (ref "U2") (pin "5") (pinfunction "VDD_RTC_5") (pintype "passive+no_connect"))
    )
    (net (code "52") (name "unconnected-(X1-Pad5)") (class "Default")
      (node (ref "X1") (pin "5") (pinfunction "5_5") (pintype "passive+no_connect"))
    )
    (net (code "53") (name "unconnected-(X1-Pad6)") (class "Default")
      (node (ref "X1") (pin "6") (pinfunction "6_6") (pintype "passive+no_connect"))
    )
  )
)
